# USB_Interface.net
KiCad netlist of a schematic drawn in Altium Designer
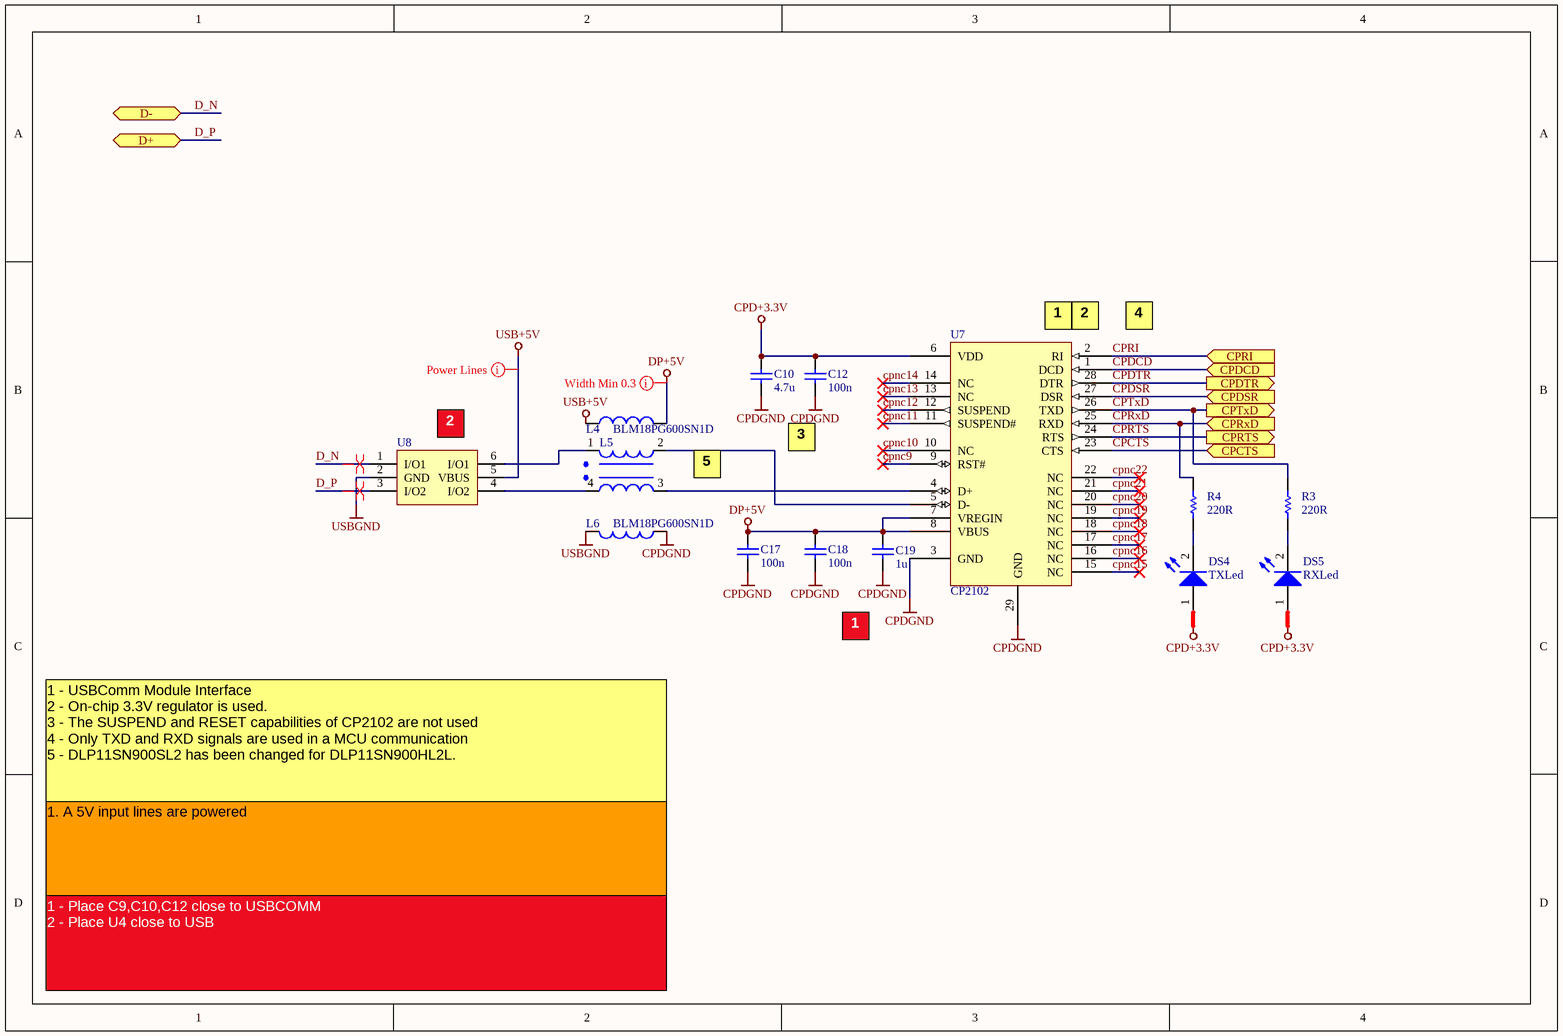
[diagram p0: USB Interface.SchDoc]

(export (version "E")
  (design (tool "Eeschema 10.0.6"))
  (components
    (comp (ref "C10")
      (value "4.7u")
      (footprint "CC1608-0603")
      (description "Capacitor (Semiconductor SIM Model)")
      (fields (field (name "Comment") "Cap Semi"))
      (libsource (lib "Z1_Project") (part "Cap Semi"))
    )
    (comp (ref "C12")
      (value "100n")
      (footprint "CC-0402-AL")
      (description "Capacitor (Semiconductor SIM Model)")
      (fields (field (name "Comment") "Cap Semi"))
      (libsource (lib "Z1_Project") (part "Cap Semi"))
    )
    (comp (ref "C17")
      (value "100n")
      (footprint "CC-0402-AL")
      (description "Capacitor (Semiconductor SIM Model)")
      (fields (field (name "Comment") "Cap Semi"))
      (libsource (lib "Z1_Project") (part "Cap Semi"))
    )
    (comp (ref "C18")
      (value "100n")
      (footprint "CC-0402-AL")
      (description "Capacitor (Semiconductor SIM Model)")
      (fields (field (name "Comment") "Cap Semi"))
      (libsource (lib "Z1_Project") (part "Cap Semi"))
    )
    (comp (ref "C19")
      (value "1u")
      (footprint "CC1005-0402")
      (description "Chip capacitor, 0603, Y5V, 10V")
      (fields (field (name "Comment") "USB bus decoupling"))
      (libsource (lib "Z1_Project") (part "Cap Semi"))
    )
    (comp (ref "DS4")
      (value "TXLed")
      (footprint "LED0603")
      (description "LED 1.6X0.8MM 589NM YEL CLR SMD")
      (libsource (lib "Z1_Project") (part "LED2"))
    )
    (comp (ref "DS5")
      (value "RXLed")
      (footprint "LED0603")
      (description "LED 1.6X0.8MM 605NM ORNG CLR SMD")
      (libsource (lib "Z1_Project") (part "LED2"))
    )
    (comp (ref "L4")
      (value "BLM18PG600SN1D")
      (footprint "INDC1608-0603")
      (description "Inductor")
      (libsource (lib "Z1_Project") (part "Inductor"))
    )
    (comp (ref "L5")
      (value "DLP11SN900HL2L")
      (footprint "inductor-4pins")
      (description "Choke Coil Common Mode 150mA SMD")
      (libsource (lib "Z1_Project") (part "DLP11SN900SL2"))
    )
    (comp (ref "L6")
      (value "BLM18PG600SN1D")
      (footprint "INDC1608-0603")
      (description "Inductor")
      (libsource (lib "Z1_Project") (part "Inductor"))
    )
    (comp (ref "R3")
      (value "220R")
      (footprint "CR-0402-AL")
      (description "Semiconductor Resistor")
      (fields (field (name "MANUFACTURER") "Generic Components") (field (name "Comment") "Res Semi"))
      (libsource (lib "Z1_Project") (part "Res Semi"))
    )
    (comp (ref "R4")
      (value "220R")
      (footprint "CR-0402-AL")
      (description "Semiconductor Resistor")
      (fields (field (name "MANUFACTURER") "Generic Components") (field (name "Comment") "Res Semi"))
      (libsource (lib "Z1_Project") (part "Res Semi"))
    )
    (comp (ref "U7")
      (value "CP2102")
      (footprint "MLP-28")
      (description "USB-to-Serial Converter from Silicon Laboratories")
      (libsource (lib "Z1_Project") (part "CP2102"))
    )
    (comp (ref "U8")
      (value "ESD protection")
      (footprint "SO-G6/E2.4")
      (description "VERY LOW CAPACITANCE  ESD PROTECTION")
      (libsource (lib "Z1_Project") (part "USBLC6-2SC6"))
    )
  )
  (nets
    (net (code "1") (name "/CPCTS") (class "Default")
      (node (ref "U7") (pin "23") (pinfunction "CTS_23") (pintype "input"))
    )
    (net (code "2") (name "/CPDCD") (class "Default")
      (node (ref "U7") (pin "1") (pinfunction "DCD_1") (pintype "input"))
    )
    (net (code "3") (name "/CPDSR") (class "Default")
      (node (ref "U7") (pin "27") (pinfunction "DSR_27") (pintype "input"))
    )
    (net (code "4") (name "/CPDTR") (class "Default")
      (node (ref "U7") (pin "28") (pinfunction "DTR_28") (pintype "output"))
    )
    (net (code "5") (name "/CPRI") (class "Default")
      (node (ref "U7") (pin "2") (pinfunction "RI_2") (pintype "input"))
    )
    (net (code "6") (name "/CPRTS") (class "Default")
      (node (ref "U7") (pin "24") (pinfunction "RTS_24") (pintype "output"))
    )
    (net (code "7") (name "/CPRxD") (class "Default")
      (node (ref "R4") (pin "2") (pinfunction "2_2") (pintype "passive"))
      (node (ref "U7") (pin "25") (pinfunction "RXD_25") (pintype "input"))
    )
    (net (code "8") (name "/CPTxD") (class "Default")
      (node (ref "R3") (pin "2") (pinfunction "2_2") (pintype "passive"))
      (node (ref "U7") (pin "26") (pinfunction "TXD_26") (pintype "output"))
    )
    (net (code "9") (name "/D_N") (class "Default")
      (node (ref "U8") (pin "1") (pinfunction "I/O1_1") (pintype "passive"))
    )
    (net (code "10") (name "/D_P") (class "Default")
      (node (ref "U8") (pin "3") (pinfunction "I/O2_3") (pintype "passive"))
    )
    (net (code "11") (name "/cpnc9") (class "Default")
      (node (ref "U7") (pin "9") (pinfunction "RST#_9") (pintype "bidirectional+no_connect"))
    )
    (net (code "12") (name "/cpnc10") (class "Default")
      (node (ref "U7") (pin "10") (pinfunction "NC_10") (pintype "passive+no_connect"))
    )
    (net (code "13") (name "/cpnc11") (class "Default")
      (node (ref "U7") (pin "11") (pinfunction "SUSPEND#_11") (pintype "output+no_connect"))
    )
    (net (code "14") (name "/cpnc12") (class "Default")
      (node (ref "U7") (pin "12") (pinfunction "SUSPEND_12") (pintype "output+no_connect"))
    )
    (net (code "15") (name "/cpnc13") (class "Default")
      (node (ref "U7") (pin "13") (pinfunction "NC_13") (pintype "passive+no_connect"))
    )
    (net (code "16") (name "/cpnc14") (class "Default")
      (node (ref "U7") (pin "14") (pinfunction "NC_14") (pintype "passive+no_connect"))
    )
    (net (code "17") (name "/cpnc15") (class "Default")
      (node (ref "U7") (pin "15") (pinfunction "NC_15") (pintype "passive+no_connect"))
    )
    (net (code "18") (name "/cpnc16") (class "Default")
      (node (ref "U7") (pin "16") (pinfunction "NC_16") (pintype "passive+no_connect"))
    )
    (net (code "19") (name "/cpnc17") (class "Default")
      (node (ref "U7") (pin "17") (pinfunction "NC_17") (pintype "passive+no_connect"))
    )
    (net (code "20") (name "/cpnc18") (class "Default")
      (node (ref "U7") (pin "18") (pinfunction "NC_18") (pintype "passive+no_connect"))
    )
    (net (code "21") (name "/cpnc19") (class "Default")
      (node (ref "U7") (pin "19") (pinfunction "NC_19") (pintype "passive+no_connect"))
    )
    (net (code "22") (name "/cpnc20") (class "Default")
      (node (ref "U7") (pin "20") (pinfunction "NC_20") (pintype "passive+no_connect"))
    )
    (net (code "23") (name "/cpnc21") (class "Default")
      (node (ref "U7") (pin "21") (pinfunction "NC_21") (pintype "passive+no_connect"))
    )
    (net (code "24") (name "/cpnc22") (class "Default")
      (node (ref "U7") (pin "22") (pinfunction "NC_22") (pintype "passive+no_connect"))
    )
    (net (code "25") (name "CPD+3.3V") (class "Default")
      (node (ref "C10") (pin "2") (pinfunction "2_2") (pintype "passive"))
      (node (ref "C12") (pin "1") (pinfunction "1_1") (pintype "passive"))
      (node (ref "DS4") (pin "1") (pinfunction "A_1") (pintype "passive"))
      (node (ref "DS5") (pin "1") (pinfunction "A_1") (pintype "passive"))
      (node (ref "U7") (pin "6") (pinfunction "VDD_6") (pintype "power_in"))
    )
    (net (code "26") (name "CPDGND") (class "Default")
      (node (ref "C10") (pin "1") (pinfunction "1_1") (pintype "passive"))
      (node (ref "C12") (pin "2") (pinfunction "2_2") (pintype "passive"))
      (node (ref "C17") (pin "2") (pinfunction "2_2") (pintype "passive"))
      (node (ref "C18") (pin "2") (pinfunction "2_2") (pintype "passive"))
      (node (ref "C19") (pin "2") (pinfunction "2_2") (pintype "passive"))
      (node (ref "L6") (pin "1") (pinfunction "1_1") (pintype "passive"))
      (node (ref "U7") (pin "29") (pinfunction "GND_29") (pintype "power_in"))
      (node (ref "U7") (pin "3") (pinfunction "GND_3") (pintype "power_in"))
    )
    (net (code "27") (name "DP+5V") (class "Default")
      (node (ref "C17") (pin "1") (pinfunction "1_1") (pintype "passive"))
      (node (ref "C18") (pin "1") (pinfunction "1_1") (pintype "passive"))
      (node (ref "C19") (pin "1") (pinfunction "1_1") (pintype "passive"))
      (node (ref "L4") (pin "2") (pinfunction "2_2") (pintype "passive"))
      (node (ref "U7") (pin "7") (pinfunction "VREGIN_7") (pintype "power_in"))
      (node (ref "U7") (pin "8") (pinfunction "VBUS_8") (pintype "power_in"))
    )
    (net (code "28") (name "Net-(DS4-K)") (class "Default")
      (node (ref "DS4") (pin "2") (pinfunction "K_2") (pintype "passive"))
      (node (ref "R4") (pin "1") (pinfunction "1_1") (pintype "passive"))
    )
    (net (code "29") (name "Net-(DS5-K)") (class "Default")
      (node (ref "DS5") (pin "2") (pinfunction "K_2") (pintype "passive"))
      (node (ref "R3") (pin "1") (pinfunction "1_1") (pintype "passive"))
    )
    (net (code "30") (name "Net-(L5-Pad1)") (class "Default")
      (node (ref "L5") (pin "1") (pinfunction "1_1") (pintype "passive"))
      (node (ref "U8") (pin "6") (pinfunction "I/O1_6") (pintype "passive"))
    )
    (net (code "31") (name "Net-(L5-Pad4)") (class "Default")
      (node (ref "L5") (pin "4") (pinfunction "4_4") (pintype "passive"))
      (node (ref "U8") (pin "4") (pinfunction "I/O2_4") (pintype "passive"))
    )
    (net (code "32") (name "Net-(U7-D+)") (class "Default")
      (node (ref "L5") (pin "3") (pinfunction "3_3") (pintype "passive"))
      (node (ref "U7") (pin "4") (pinfunction "D+_4") (pintype "bidirectional"))
    )
    (net (code "33") (name "Net-(U7-D-)") (class "Default")
      (node (ref "L5") (pin "2") (pinfunction "2_2") (pintype "passive"))
      (node (ref "U7") (pin "5") (pinfunction "D-_5") (pintype "bidirectional"))
    )
    (net (code "34") (name "USB+5V") (class "Default")
      (node (ref "L4") (pin "1") (pinfunction "1_1") (pintype "passive"))
      (node (ref "U8") (pin "5") (pinfunction "VBUS_5") (pintype "passive"))
    )
    (net (code "35") (name "USBGND") (class "Default")
      (node (ref "L6") (pin "2") (pinfunction "2_2") (pintype "passive"))
      (node (ref "U8") (pin "2") (pinfunction "GND_2") (pintype "passive"))
    )
  )
)
